# main.net
KiCad netlist of a schematic drawn in EAGLE
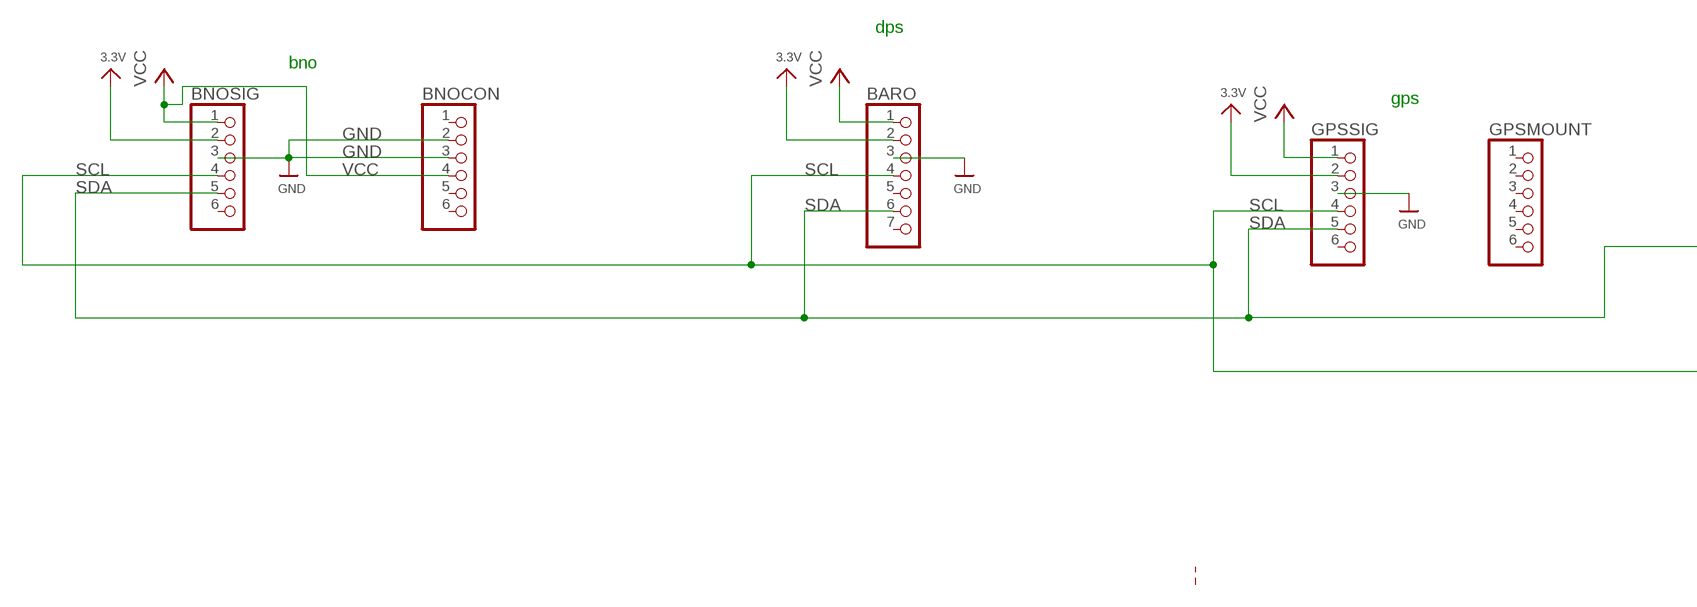
[diagram p0: schematic, sheet 1, part 1 of 2]
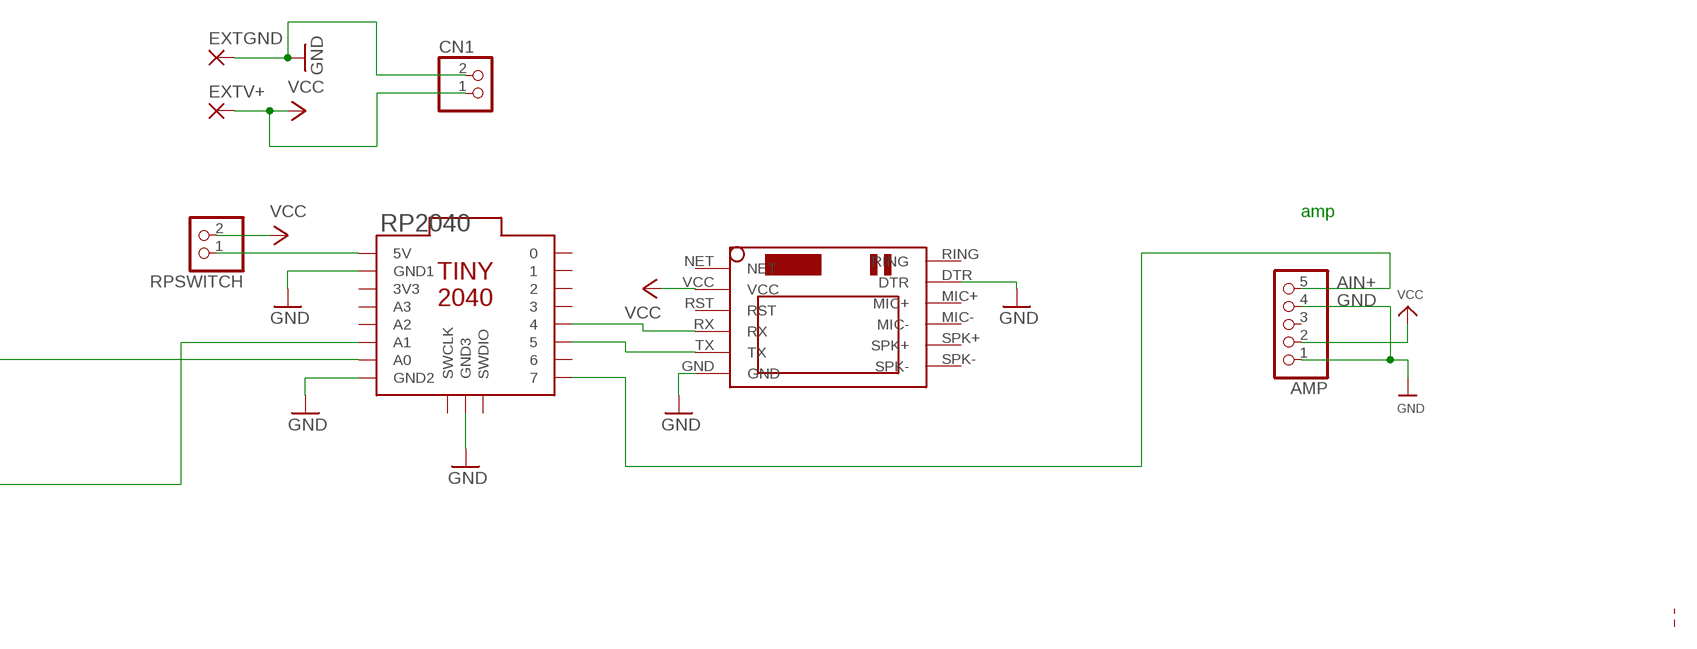
[diagram p1: schematic, sheet 1, part 2 of 2]

(export (version "E")
  (design (tool "Eeschema 10.0.6"))
  (components
    (comp (ref "AMP")
      (value "HEADER-1X570MIL")
      (footprint "eagle-import:1X05_ROUND_70")
      (libsource (lib "eagle-import") (part "HEADER-1X570MIL"))
    )
    (comp (ref "BARO")
      (value "HEADER-1X770MIL")
      (footprint "eagle-import:1X07_ROUND_70")
      (libsource (lib "eagle-import") (part "HEADER-1X770MIL"))
    )
    (comp (ref "BNOCON")
      (value "HEADER-1X670MIL")
      (footprint "eagle-import:1X06_ROUND_70")
      (libsource (lib "eagle-import") (part "HEADER-1X670MIL"))
    )
    (comp (ref "BNOSIG")
      (value "HEADER-1X670MIL")
      (footprint "eagle-import:1X06_ROUND_70")
      (libsource (lib "eagle-import") (part "HEADER-1X670MIL"))
    )
    (comp (ref "CN1")
      (value "JST_2PIN-THM-RA")
      (footprint "eagle-import:JST-PH-2-THM-RA")
      (libsource (lib "eagle-import") (part "JST_2PIN-THM-RA"))
    )
    (comp (ref "EXTGND")
      (value "SMD5")
      (footprint "eagle-import:SMD2,54-5,08")
      (libsource (lib "eagle-import") (part "SMD5"))
    )
    (comp (ref "EXTV+")
      (value "SMD5")
      (footprint "eagle-import:SMD2,54-5,08")
      (libsource (lib "eagle-import") (part "SMD5"))
    )
    (comp (ref "GPSMOUNT")
      (value "HEADER-1X670MIL")
      (footprint "eagle-import:1X06_ROUND_70")
      (libsource (lib "eagle-import") (part "HEADER-1X670MIL"))
    )
    (comp (ref "GPSSIG")
      (value "HEADER-1X670MIL")
      (footprint "eagle-import:1X06_ROUND_70")
      (libsource (lib "eagle-import") (part "HEADER-1X670MIL"))
    )
    (comp (ref "RP2040")
      (value "TINY2040")
      (footprint "eagle-import:TINY2040")
      (libsource (lib "eagle-import") (part "TINY2040"))
    )
    (comp (ref "RPSWITCH")
      (value "PINHD-1X2")
      (footprint "eagle-import:1X02")
      (libsource (lib "eagle-import") (part "PINHD-1X2"))
    )
    (comp (ref "U$1")
      (value "SIM800LMODULE")
      (footprint "eagle-import:SIM800LMODULE")
      (libsource (lib "eagle-import") (part "SIM800LMODULE"))
    )
  )
  (nets
    (net (code "1") (name "/AIN+") (class "Default")
      (node (ref "AMP") (pin "5") (pinfunction "5_5") (pintype "passive"))
      (node (ref "RP2040") (pin "7") (pinfunction "7_7") (pintype "bidirectional"))
    )
    (net (code "2") (name "/SCL") (class "Default")
      (node (ref "BARO") (pin "4") (pinfunction "4_4") (pintype "passive"))
      (node (ref "BNOSIG") (pin "4") (pinfunction "4_4") (pintype "passive"))
      (node (ref "GPSSIG") (pin "4") (pinfunction "4_4") (pintype "passive"))
      (node (ref "RP2040") (pin "A1") (pinfunction "A1_A1") (pintype "bidirectional"))
    )
    (net (code "3") (name "/SDA") (class "Default")
      (node (ref "BARO") (pin "6") (pinfunction "6_6") (pintype "passive"))
      (node (ref "BNOSIG") (pin "5") (pinfunction "5_5") (pintype "passive"))
      (node (ref "GPSSIG") (pin "5") (pinfunction "5_5") (pintype "passive"))
      (node (ref "RP2040") (pin "A0") (pinfunction "A0_A0") (pintype "bidirectional"))
    )
    (net (code "4") (name "3.3V") (class "Default")
      (node (ref "BARO") (pin "2") (pinfunction "2_2") (pintype "passive"))
      (node (ref "BNOSIG") (pin "2") (pinfunction "2_2") (pintype "passive"))
      (node (ref "GPSSIG") (pin "2") (pinfunction "2_2") (pintype "passive"))
    )
    (net (code "5") (name "GND") (class "Default")
      (node (ref "AMP") (pin "1") (pinfunction "1_1") (pintype "passive"))
      (node (ref "AMP") (pin "4") (pinfunction "4_4") (pintype "passive"))
      (node (ref "BARO") (pin "3") (pinfunction "3_3") (pintype "passive"))
      (node (ref "BNOCON") (pin "2") (pinfunction "2_2") (pintype "passive"))
      (node (ref "BNOCON") (pin "3") (pinfunction "3_3") (pintype "passive"))
      (node (ref "BNOSIG") (pin "3") (pinfunction "3_3") (pintype "passive"))
      (node (ref "CN1") (pin "2") (pinfunction "1_2") (pintype "passive"))
      (node (ref "EXTGND") (pin "1") (pinfunction "P_1") (pintype "passive"))
      (node (ref "GPSSIG") (pin "3") (pinfunction "3_3") (pintype "passive"))
      (node (ref "RP2040") (pin "GND1") (pinfunction "GND1_GND1") (pintype "bidirectional"))
      (node (ref "RP2040") (pin "GND2") (pinfunction "GND2_GND2") (pintype "bidirectional"))
      (node (ref "RP2040") (pin "GND3") (pinfunction "GND3_GND3") (pintype "bidirectional"))
      (node (ref "U$1") (pin "DTR") (pinfunction "DTR_DTR") (pintype "bidirectional"))
      (node (ref "U$1") (pin "GND") (pinfunction "GND_GND") (pintype "bidirectional"))
    )
    (net (code "6") (name "Net-(RP2040-Pad4)") (class "Default")
      (node (ref "RP2040") (pin "4") (pinfunction "4_4") (pintype "bidirectional"))
      (node (ref "U$1") (pin "RX") (pinfunction "RX_RX") (pintype "bidirectional"))
    )
    (net (code "7") (name "Net-(RP2040-Pad5)") (class "Default")
      (node (ref "RP2040") (pin "5") (pinfunction "5_5") (pintype "bidirectional"))
      (node (ref "U$1") (pin "TX") (pinfunction "TX_TX") (pintype "bidirectional"))
    )
    (net (code "8") (name "Net-(RP2040-Pad5V)") (class "Default")
      (node (ref "RP2040") (pin "5V") (pinfunction "5V_5V") (pintype "bidirectional"))
      (node (ref "RPSWITCH") (pin "1") (pinfunction "1_1") (pintype "passive"))
    )
    (net (code "9") (name "VCC") (class "Default")
      (node (ref "AMP") (pin "2") (pinfunction "2_2") (pintype "passive"))
      (node (ref "BARO") (pin "1") (pinfunction "1_1") (pintype "passive"))
      (node (ref "BNOCON") (pin "4") (pinfunction "4_4") (pintype "passive"))
      (node (ref "BNOSIG") (pin "1") (pinfunction "1_1") (pintype "passive"))
      (node (ref "CN1") (pin "1") (pinfunction "2_1") (pintype "passive"))
      (node (ref "EXTV+") (pin "1") (pinfunction "P_1") (pintype "passive"))
      (node (ref "GPSSIG") (pin "1") (pinfunction "1_1") (pintype "passive"))
      (node (ref "RPSWITCH") (pin "2") (pinfunction "2_2") (pintype "passive"))
      (node (ref "U$1") (pin "VCC") (pinfunction "VCC_VCC") (pintype "bidirectional"))
    )
    (net (code "10") (name "unconnected-(AMP-Pad3)") (class "Default")
      (node (ref "AMP") (pin "3") (pinfunction "3_3") (pintype "passive"))
    )
    (net (code "11") (name "unconnected-(BARO-Pad5)") (class "Default")
      (node (ref "BARO") (pin "5") (pinfunction "5_5") (pintype "passive"))
    )
    (net (code "12") (name "unconnected-(BARO-Pad7)") (class "Default")
      (node (ref "BARO") (pin "7") (pinfunction "7_7") (pintype "passive"))
    )
    (net (code "13") (name "unconnected-(BNOCON-Pad1)") (class "Default")
      (node (ref "BNOCON") (pin "1") (pinfunction "1_1") (pintype "passive"))
    )
    (net (code "14") (name "unconnected-(BNOCON-Pad5)") (class "Default")
      (node (ref "BNOCON") (pin "5") (pinfunction "5_5") (pintype "passive"))
    )
    (net (code "15") (name "unconnected-(BNOCON-Pad6)") (class "Default")
      (node (ref "BNOCON") (pin "6") (pinfunction "6_6") (pintype "passive"))
    )
    (net (code "16") (name "unconnected-(BNOSIG-Pad6)") (class "Default")
      (node (ref "BNOSIG") (pin "6") (pinfunction "6_6") (pintype "passive"))
    )
    (net (code "17") (name "unconnected-(GPSMOUNT-Pad1)") (class "Default")
      (node (ref "GPSMOUNT") (pin "1") (pinfunction "1_1") (pintype "passive"))
    )
    (net (code "18") (name "unconnected-(GPSMOUNT-Pad2)") (class "Default")
      (node (ref "GPSMOUNT") (pin "2") (pinfunction "2_2") (pintype "passive"))
    )
    (net (code "19") (name "unconnected-(GPSMOUNT-Pad3)") (class "Default")
      (node (ref "GPSMOUNT") (pin "3") (pinfunction "3_3") (pintype "passive"))
    )
    (net (code "20") (name "unconnected-(GPSMOUNT-Pad4)") (class "Default")
      (node (ref "GPSMOUNT") (pin "4") (pinfunction "4_4") (pintype "passive"))
    )
    (net (code "21") (name "unconnected-(GPSMOUNT-Pad5)") (class "Default")
      (node (ref "GPSMOUNT") (pin "5") (pinfunction "5_5") (pintype "passive"))
    )
    (net (code "22") (name "unconnected-(GPSMOUNT-Pad6)") (class "Default")
      (node (ref "GPSMOUNT") (pin "6") (pinfunction "6_6") (pintype "passive"))
    )
    (net (code "23") (name "unconnected-(GPSSIG-Pad6)") (class "Default")
      (node (ref "GPSSIG") (pin "6") (pinfunction "6_6") (pintype "passive"))
    )
    (net (code "24") (name "unconnected-(RP2040-Pad0)") (class "Default")
      (node (ref "RP2040") (pin "0") (pinfunction "0_0") (pintype "bidirectional"))
    )
    (net (code "25") (name "unconnected-(RP2040-Pad1)") (class "Default")
      (node (ref "RP2040") (pin "1") (pinfunction "1_1") (pintype "bidirectional"))
    )
    (net (code "26") (name "unconnected-(RP2040-Pad2)") (class "Default")
      (node (ref "RP2040") (pin "2") (pinfunction "2_2") (pintype "bidirectional"))
    )
    (net (code "27") (name "unconnected-(RP2040-Pad3)") (class "Default")
      (node (ref "RP2040") (pin "3") (pinfunction "3_3") (pintype "bidirectional"))
    )
    (net (code "28") (name "unconnected-(RP2040-Pad3V3)") (class "Default")
      (node (ref "RP2040") (pin "3V3") (pinfunction "3V3_3V3") (pintype "bidirectional"))
    )
    (net (code "29") (name "unconnected-(RP2040-Pad6)") (class "Default")
      (node (ref "RP2040") (pin "6") (pinfunction "6_6") (pintype "bidirectional"))
    )
    (net (code "30") (name "unconnected-(RP2040-PadA2)") (class "Default")
      (node (ref "RP2040") (pin "A2") (pinfunction "A2_A2") (pintype "bidirectional"))
    )
    (net (code "31") (name "unconnected-(RP2040-PadA3)") (class "Default")
      (node (ref "RP2040") (pin "A3") (pinfunction "A3_A3") (pintype "bidirectional"))
    )
    (net (code "32") (name "unconnected-(RP2040-PadSWCLK)") (class "Default")
      (node (ref "RP2040") (pin "SWCLK") (pinfunction "SWCLK_SWCLK") (pintype "bidirectional"))
    )
    (net (code "33") (name "unconnected-(RP2040-PadSWDIO)") (class "Default")
      (node (ref "RP2040") (pin "SWDIO") (pinfunction "SWDIO_SWDIO") (pintype "bidirectional"))
    )
    (net (code "34") (name "unconnected-(U$1-PadMIC+)") (class "Default")
      (node (ref "U$1") (pin "MIC+") (pinfunction "MIC+_MIC+") (pintype "bidirectional"))
    )
    (net (code "35") (name "unconnected-(U$1-PadMIC-)") (class "Default")
      (node (ref "U$1") (pin "MIC-") (pinfunction "MIC-_MIC-") (pintype "bidirectional"))
    )
    (net (code "36") (name "unconnected-(U$1-PadNET)") (class "Default")
      (node (ref "U$1") (pin "NET") (pinfunction "NET_NET") (pintype "bidirectional"))
    )
    (net (code "37") (name "unconnected-(U$1-PadRING)") (class "Default")
      (node (ref "U$1") (pin "RING") (pinfunction "RING_RING") (pintype "bidirectional"))
    )
    (net (code "38") (name "unconnected-(U$1-PadRST)") (class "Default")
      (node (ref "U$1") (pin "RST") (pinfunction "RST_RST") (pintype "bidirectional"))
    )
    (net (code "39") (name "unconnected-(U$1-PadSPK+)") (class "Default")
      (node (ref "U$1") (pin "SPK+") (pinfunction "SPK+_SPK+") (pintype "bidirectional"))
    )
    (net (code "40") (name "unconnected-(U$1-PadSPK-)") (class "Default")
      (node (ref "U$1") (pin "SPK-") (pinfunction "SPK-_SPK-") (pintype "bidirectional"))
    )
  )
)
